# Polarity_Select_12Vinput.net
KiCad netlist of a schematic drawn in Altium Designer
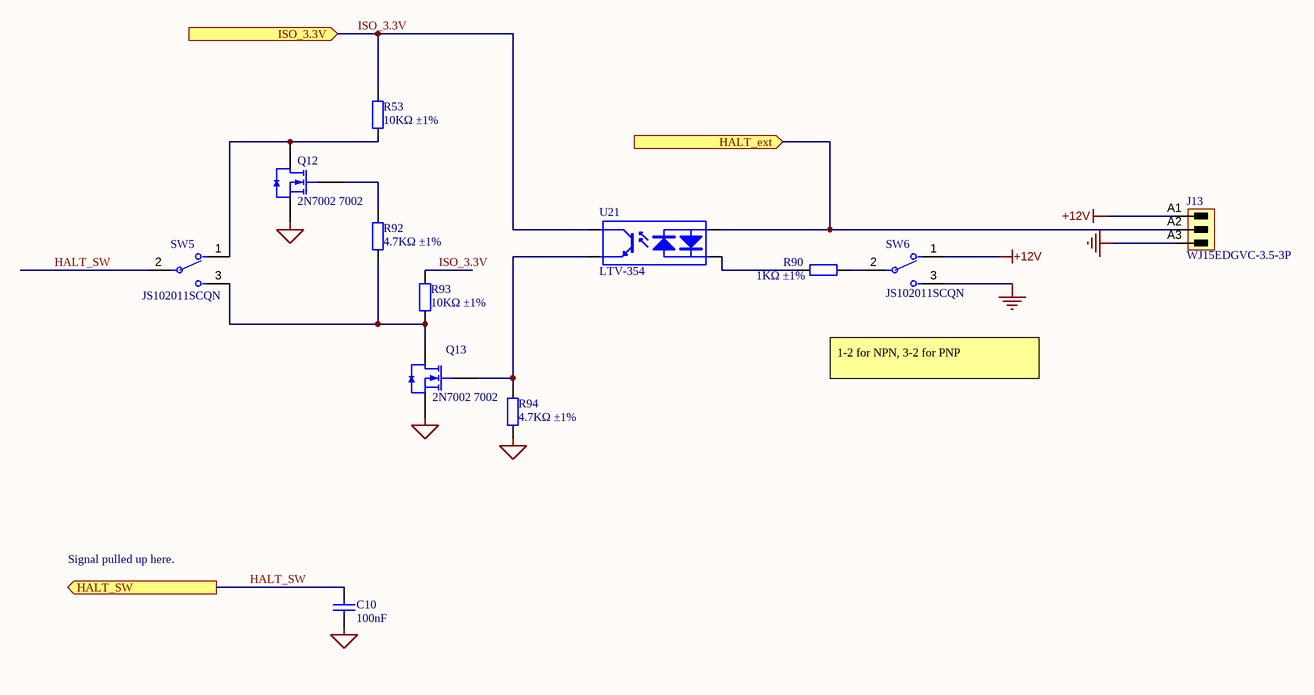
[diagram p0: Polarity_Select_12Vinput.SchDoc]

(export (version "E")
  (design (tool "Eeschema 10.0.6"))
  (components
    (comp (ref "C10")
      (value "100nF")
      (footprint "0402_C")
      (description "Chip capacitors")
      (fields
        (field (name "MANUFACTURER") "Samsung Electro-Mechanics")
        (field (name "PARTNUMBER") "CL05B104KO5NNNC")
      )
      (libsource (lib "Cap") (part "0402 100nF (104) 10% 16V"))
    )
    (comp (ref "J13")
      (value "WJ15EDGVC-3.5-3P")
      (footprint "691321100003 - 3.5mm  3p")
      (fields (field (name "MANUFACTURER") "Weidmueller"))
      (libsource (lib "Universal_CNC_Breakout") (part "3.5mm Terminal Header 3p"))
    )
    (comp (ref "Q12")
      (value "2N7002 7002")
      (footprint "SOT-23(SOT-23-3)")
      (description "MOS(场效应管)")
      (libsource (lib "MOS") (part "2N7002 7002"))
    )
    (comp (ref "Q13")
      (value "2N7002 7002")
      (footprint "SOT-23(SOT-23-3)")
      (description "MOS(场效应管)")
      (libsource (lib "MOS") (part "2N7002 7002"))
    )
    (comp (ref "R53")
      (value "10KΩ ±1%")
      (footprint "0402_R")
      (description "Chip resistor")
      (fields (field (name "MANUFACTURER") "Uniroyal Elec") (field (name "PARTNUMBER") "0402WGF1002TCE"))
      (libsource (lib "RES") (part "0402 10K (1002) 1%"))
    )
    (comp (ref "R90")
      (value "1KΩ ±1%")
      (footprint "0402_R")
      (description "Chip resistor")
      (fields (field (name "MANUFACTURER") "Uniroyal Elec") (field (name "PARTNUMBER") "0402WGF1001TCE"))
      (libsource (lib "RES") (part "0402 1K (1001) 1%"))
    )
    (comp (ref "R92")
      (value "4.7KΩ ±1%")
      (footprint "0402_R")
      (description "Chip resistor")
      (fields (field (name "MANUFACTURER") "Uniroyal Elec") (field (name "PARTNUMBER") "0402WGF4701TCE"))
      (libsource (lib "RES") (part "0402 4.7K (4701) 1%"))
    )
    (comp (ref "R93")
      (value "10KΩ ±1%")
      (footprint "0402_R")
      (description "Chip resistor")
      (fields (field (name "MANUFACTURER") "Uniroyal Elec") (field (name "PARTNUMBER") "0402WGF1002TCE"))
      (libsource (lib "RES") (part "0402 10K (1002) 1%"))
    )
    (comp (ref "R94")
      (value "4.7KΩ ±1%")
      (footprint "0402_R")
      (description "Chip resistor")
      (fields (field (name "MANUFACTURER") "Uniroyal Elec") (field (name "PARTNUMBER") "0402WGF4701TCE"))
      (libsource (lib "RES") (part "0402 4.7K (4701) 1%"))
    )
    (comp (ref "SW5")
      (value "JS102011SCQN")
      (footprint "FP-JS102011SCQN-MFG")
      (description "Switch Slide SPDT Top Slide 0.3A 30VDC Gull Wing SMD T/R")
      (libsource (lib "Cambridge Mobile Telematics, Inc") (part "39e195cbbadc85d1df0d7eb6847d379"))
    )
    (comp (ref "SW6")
      (value "JS102011SCQN")
      (footprint "FP-JS102011SCQN-MFG")
      (description "Switch Slide SPDT Top Slide 0.3A 30VDC Gull Wing SMD T/R")
      (libsource (lib "Cambridge Mobile Telematics, Inc") (part "39e195cbbadc85d1df0d7eb6847d379"))
    )
    (comp (ref "U21")
      (value "LTV-354")
      (footprint "Miscellaneous Devices LC:SOP-4_P2.54")
      (libsource (lib "IC") (part "LTV-354"))
    )
  )
  (nets
    (net (code "1") (name "+12V") (class "Default")
      (node (ref "J13") (pin "A1") (pinfunction "A1_A1") (pintype "passive"))
      (node (ref "SW6") (pin "1") (pinfunction "1_1") (pintype "passive"))
    )
    (net (code "2") (name "/HALT_SW") (class "Default")
      (node (ref "C10") (pin "2") (pinfunction "2_2") (pintype "passive"))
      (node (ref "SW5") (pin "2") (pinfunction "C_2") (pintype "passive"))
    )
    (net (code "3") (name "/HALT_ext") (class "Default")
      (node (ref "J13") (pin "A2") (pinfunction "A2_A2") (pintype "passive"))
      (node (ref "U21") (pin "1") (pinfunction "A_1") (pintype "passive"))
    )
    (net (code "4") (name "/ISO_3.3V") (class "Default")
      (node (ref "R53") (pin "2") (pinfunction "2_2") (pintype "passive"))
      (node (ref "R93") (pin "2") (pinfunction "2_2") (pintype "passive"))
      (node (ref "U21") (pin "4") (pinfunction "C_4") (pintype "passive"))
    )
    (net (code "5") (name "GND") (class "Default")
      (node (ref "J13") (pin "A3") (pinfunction "A3_A3") (pintype "passive"))
      (node (ref "SW6") (pin "3") (pinfunction "3_3") (pintype "passive"))
    )
    (net (code "6") (name "MCU_GND") (class "Default")
      (node (ref "C10") (pin "1") (pinfunction "1_1") (pintype "passive"))
      (node (ref "Q12") (pin "2") (pinfunction "S_2") (pintype "passive"))
      (node (ref "Q13") (pin "2") (pinfunction "S_2") (pintype "passive"))
      (node (ref "R94") (pin "1") (pinfunction "1_1") (pintype "passive"))
    )
    (net (code "7") (name "Net-(Q12-D)") (class "Default")
      (node (ref "Q12") (pin "3") (pinfunction "D_3") (pintype "passive"))
      (node (ref "R53") (pin "1") (pinfunction "1_1") (pintype "passive"))
      (node (ref "SW5") (pin "1") (pinfunction "1_1") (pintype "passive"))
    )
    (net (code "8") (name "Net-(Q12-G)") (class "Default")
      (node (ref "Q12") (pin "1") (pinfunction "G_1") (pintype "passive"))
      (node (ref "R92") (pin "2") (pinfunction "2_2") (pintype "passive"))
    )
    (net (code "9") (name "Net-(Q13-D)") (class "Default")
      (node (ref "Q13") (pin "3") (pinfunction "D_3") (pintype "passive"))
      (node (ref "R92") (pin "1") (pinfunction "1_1") (pintype "passive"))
      (node (ref "R93") (pin "1") (pinfunction "1_1") (pintype "passive"))
      (node (ref "SW5") (pin "3") (pinfunction "3_3") (pintype "passive"))
    )
    (net (code "10") (name "Net-(Q13-G)") (class "Default")
      (node (ref "Q13") (pin "1") (pinfunction "G_1") (pintype "passive"))
      (node (ref "R94") (pin "2") (pinfunction "2_2") (pintype "passive"))
      (node (ref "U21") (pin "3") (pinfunction "E_3") (pintype "passive"))
    )
    (net (code "11") (name "Net-(SW6-C)") (class "Default")
      (node (ref "R90") (pin "2") (pinfunction "2_2") (pintype "passive"))
      (node (ref "SW6") (pin "2") (pinfunction "C_2") (pintype "passive"))
    )
    (net (code "12") (name "Net-(U21-K)") (class "Default")
      (node (ref "R90") (pin "1") (pinfunction "1_1") (pintype "passive"))
      (node (ref "U21") (pin "2") (pinfunction "K_2") (pintype "passive"))
    )
  )
)
